# Beeper.net
KiCad netlist of a schematic drawn in Altium Designer
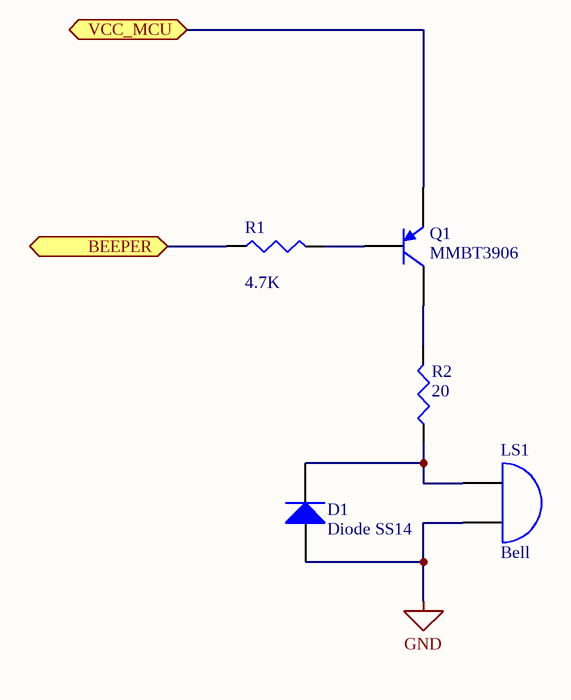
[diagram p0: Beeper.SchDoc]

(export (version "E")
  (design (tool "Eeschema 10.0.6"))
  (components
    (comp (ref "D1")
      (value "Diode SS14")
      (footprint "clock:SMA")
      (description "1 Amp General Purpose Rectifier")
      (fields (field (name "PUBLISHER") "Altium Limited"))
      (libsource (lib "Miscellaneous Devices") (part "Diode 1N4005"))
    )
    (comp (ref "LS1")
      (value "Bell")
      (footprint "clock:BEEPER_SMD")
      (description "Electrical Bell")
      (fields (field (name "PUBLISHER") "Altium Limited"))
      (libsource (lib "Miscellaneous Devices") (part "Bell"))
    )
    (comp (ref "Q1")
      (value "MMBT3906")
      (footprint "clock:SOT23-3-PNP")
      (description "PNP Bipolar Transistor")
      (fields (field (name "PUBLISHER") "Altium Limited"))
      (libsource (lib "Miscellaneous Devices") (part "PNP"))
    )
    (comp (ref "R1")
      (value "4.7K")
      (footprint "clock:0603")
      (description "Resistor")
      (fields (field (name "Comment") "Res3") (field (name "PUBLISHER") "Altium Limited"))
      (libsource (lib "Miscellaneous Devices") (part "Res3"))
    )
    (comp (ref "R2")
      (value "20")
      (footprint "clock:0603")
      (description "Resistor")
      (fields (field (name "Comment") "Res3") (field (name "PUBLISHER") "Altium Limited"))
      (libsource (lib "Miscellaneous Devices") (part "Res3"))
    )
  )
  (nets
    (net (code "1") (name "/BEEPER") (class "Default")
      (node (ref "R1") (pin "1") (pinfunction "1_1") (pintype "passive"))
    )
    (net (code "2") (name "/VCC_MCU") (class "Default")
      (node (ref "Q1") (pin "3") (pinfunction "E_3") (pintype "passive"))
    )
    (net (code "3") (name "GND") (class "Default")
      (node (ref "D1") (pin "1") (pinfunction "A_1") (pintype "passive"))
      (node (ref "LS1") (pin "2") (pinfunction "B_2") (pintype "passive"))
    )
    (net (code "4") (name "Net-(D1-K)") (class "Default")
      (node (ref "D1") (pin "2") (pinfunction "K_2") (pintype "passive"))
      (node (ref "LS1") (pin "1") (pinfunction "A_1") (pintype "passive"))
      (node (ref "R2") (pin "1") (pinfunction "1_1") (pintype "passive"))
    )
    (net (code "5") (name "Net-(Q1-B)") (class "Default")
      (node (ref "Q1") (pin "2") (pinfunction "B_2") (pintype "passive"))
      (node (ref "R1") (pin "2") (pinfunction "2_2") (pintype "passive"))
    )
    (net (code "6") (name "Net-(Q1-C)") (class "Default")
      (node (ref "Q1") (pin "1") (pinfunction "C_1") (pintype "passive"))
      (node (ref "R2") (pin "2") (pinfunction "2_2") (pintype "passive"))
    )
  )
)
